# cicely_B_v1.net
KiCad netlist of a schematic drawn in EAGLE
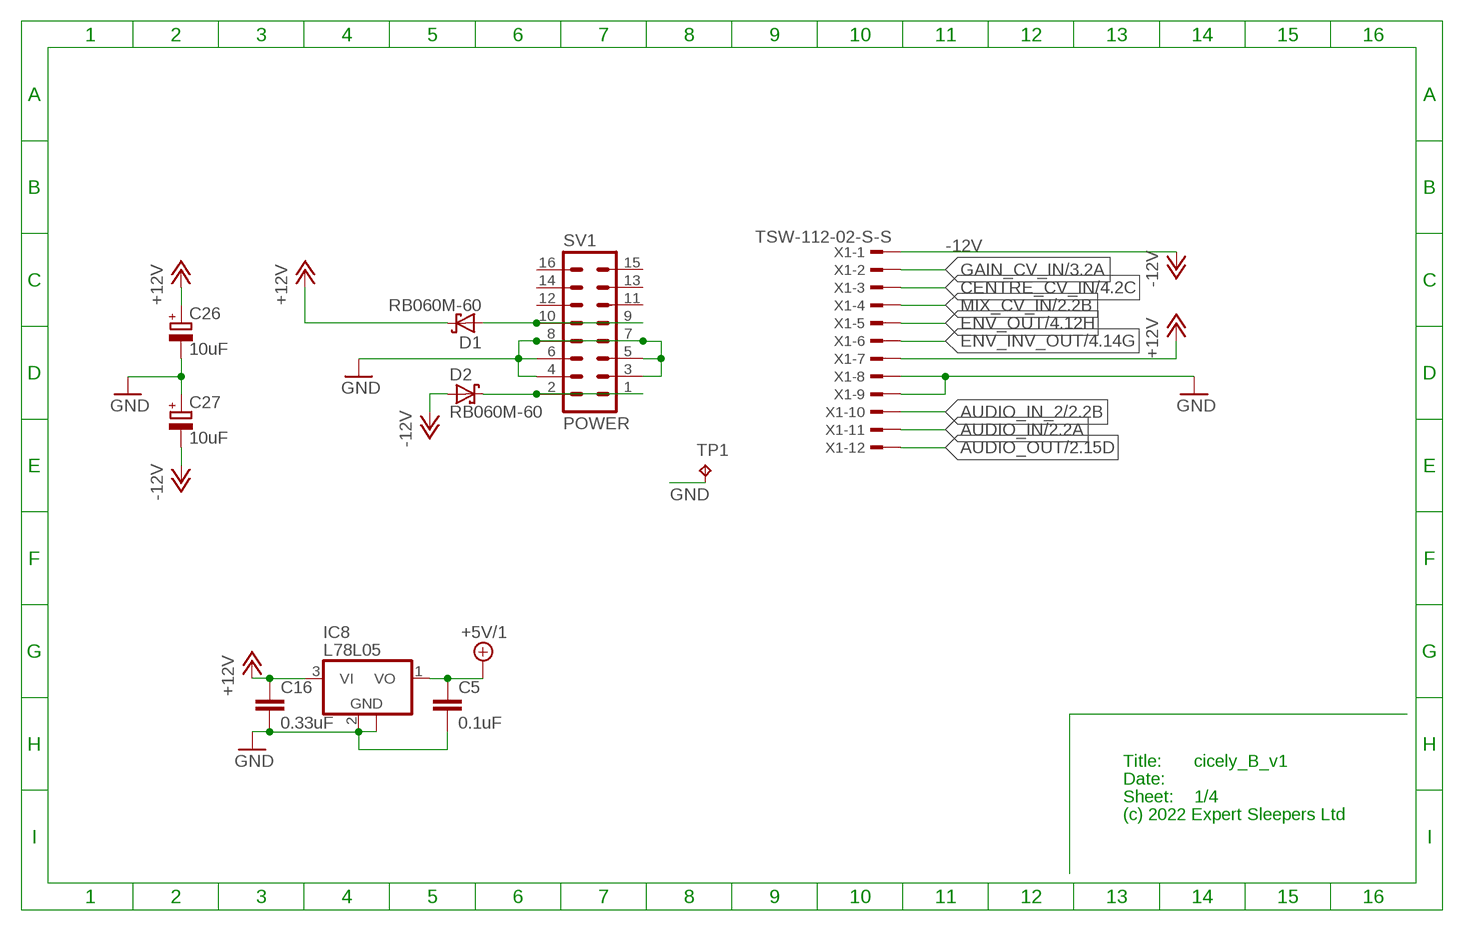
[diagram p0: schematic, sheet 1]
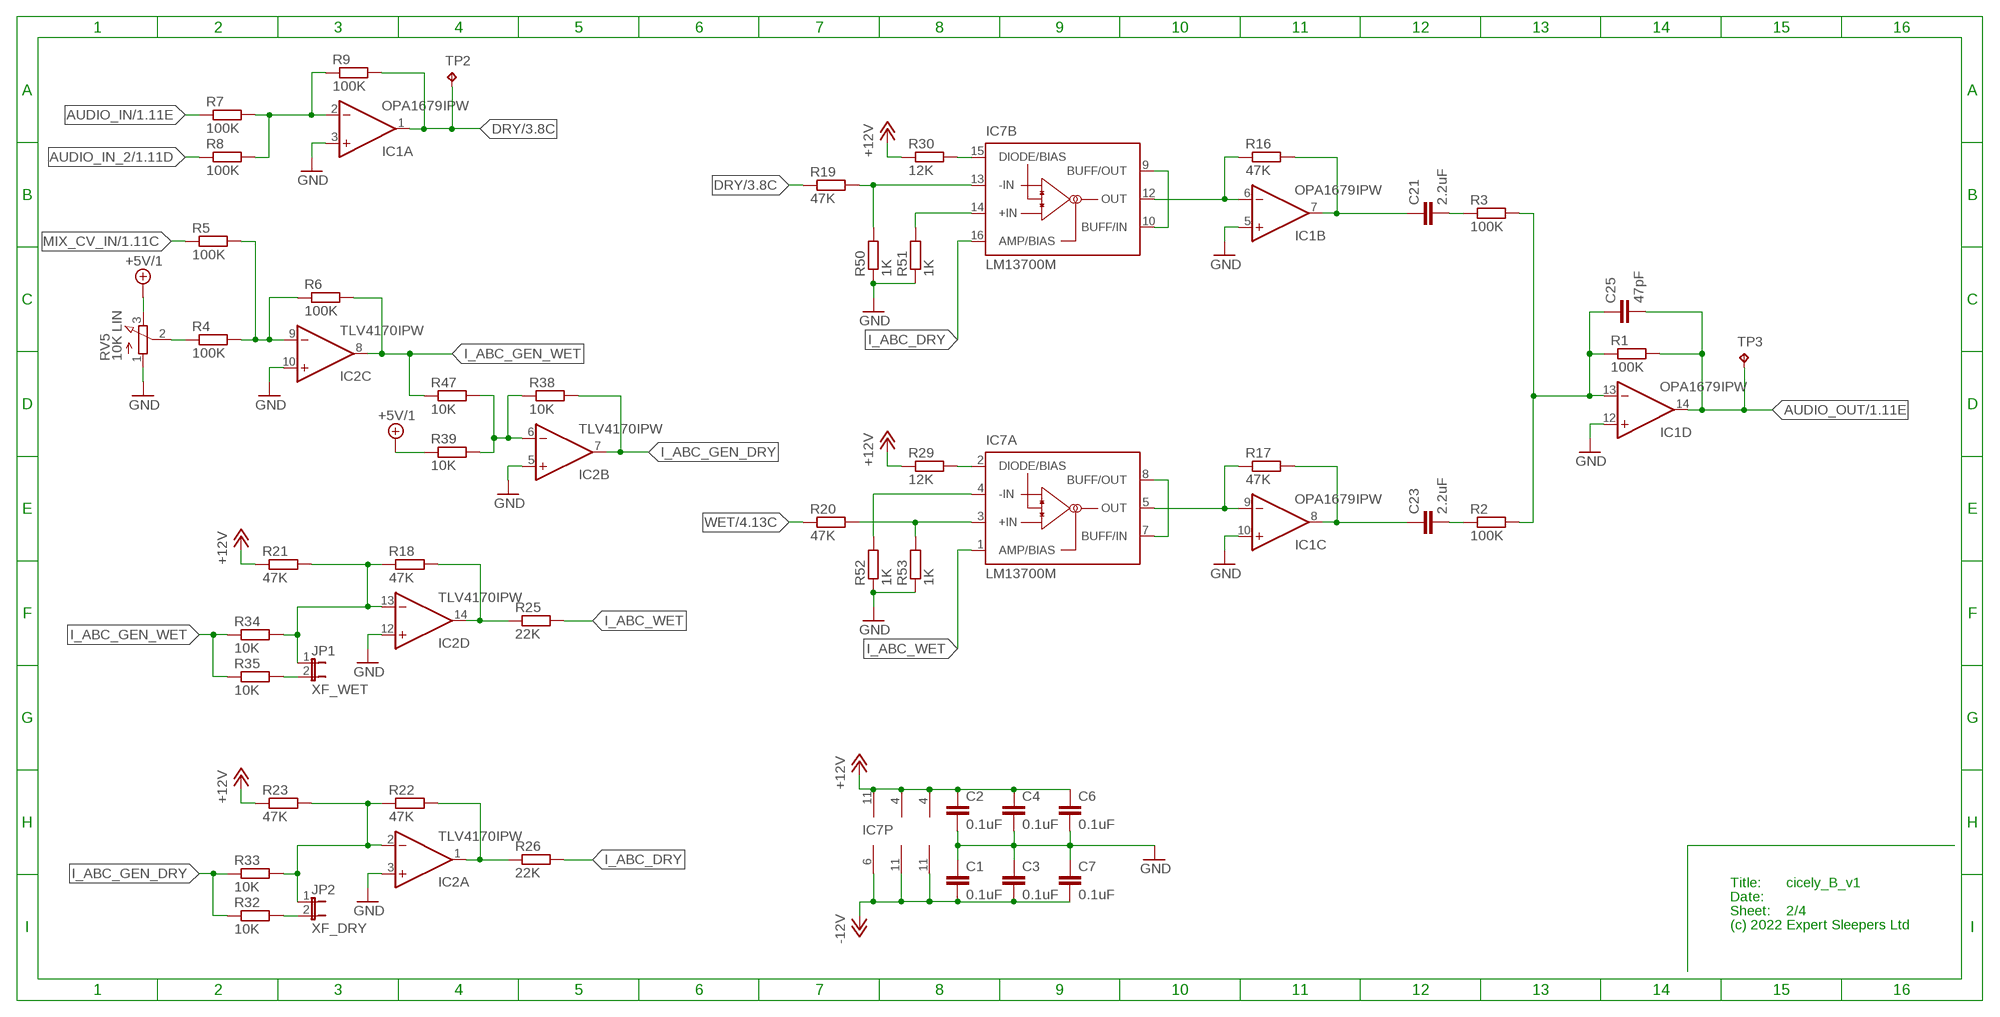
[diagram p1: schematic, sheet 2]
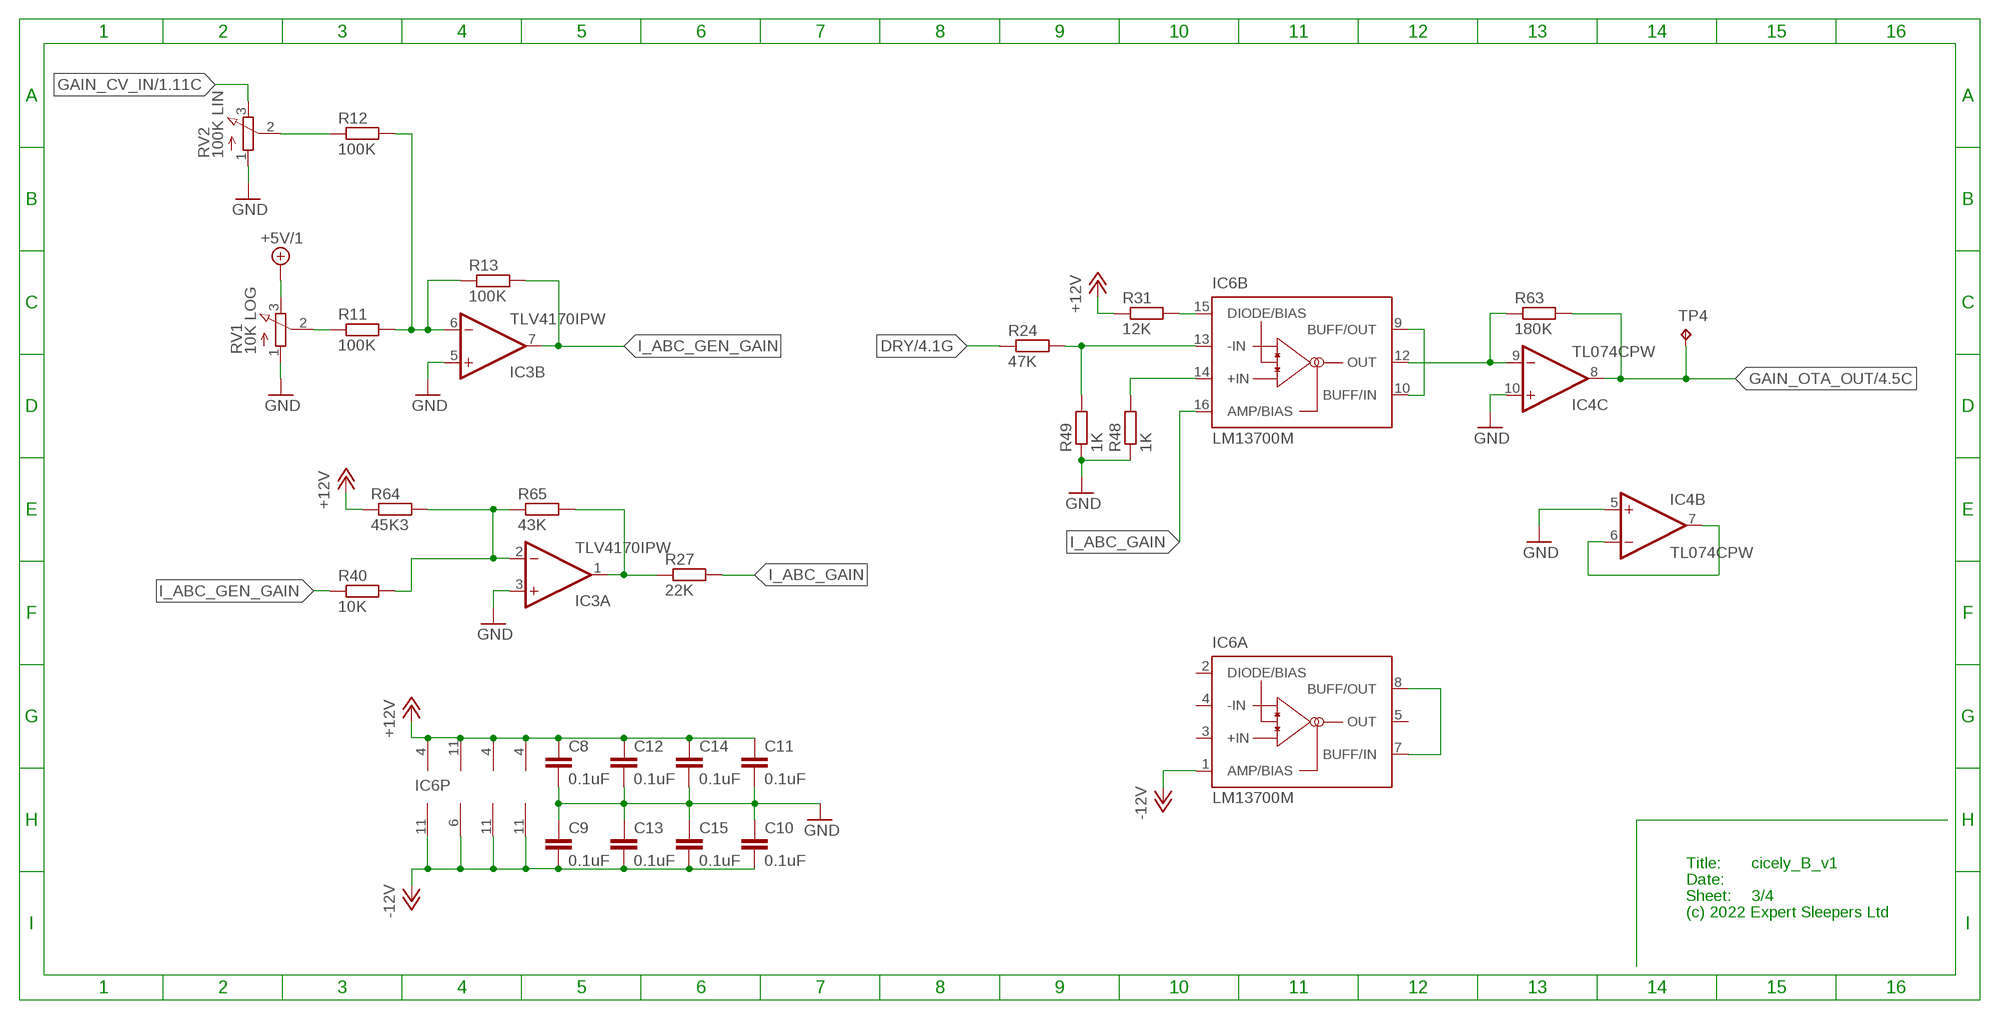
[diagram p2: schematic, sheet 3]
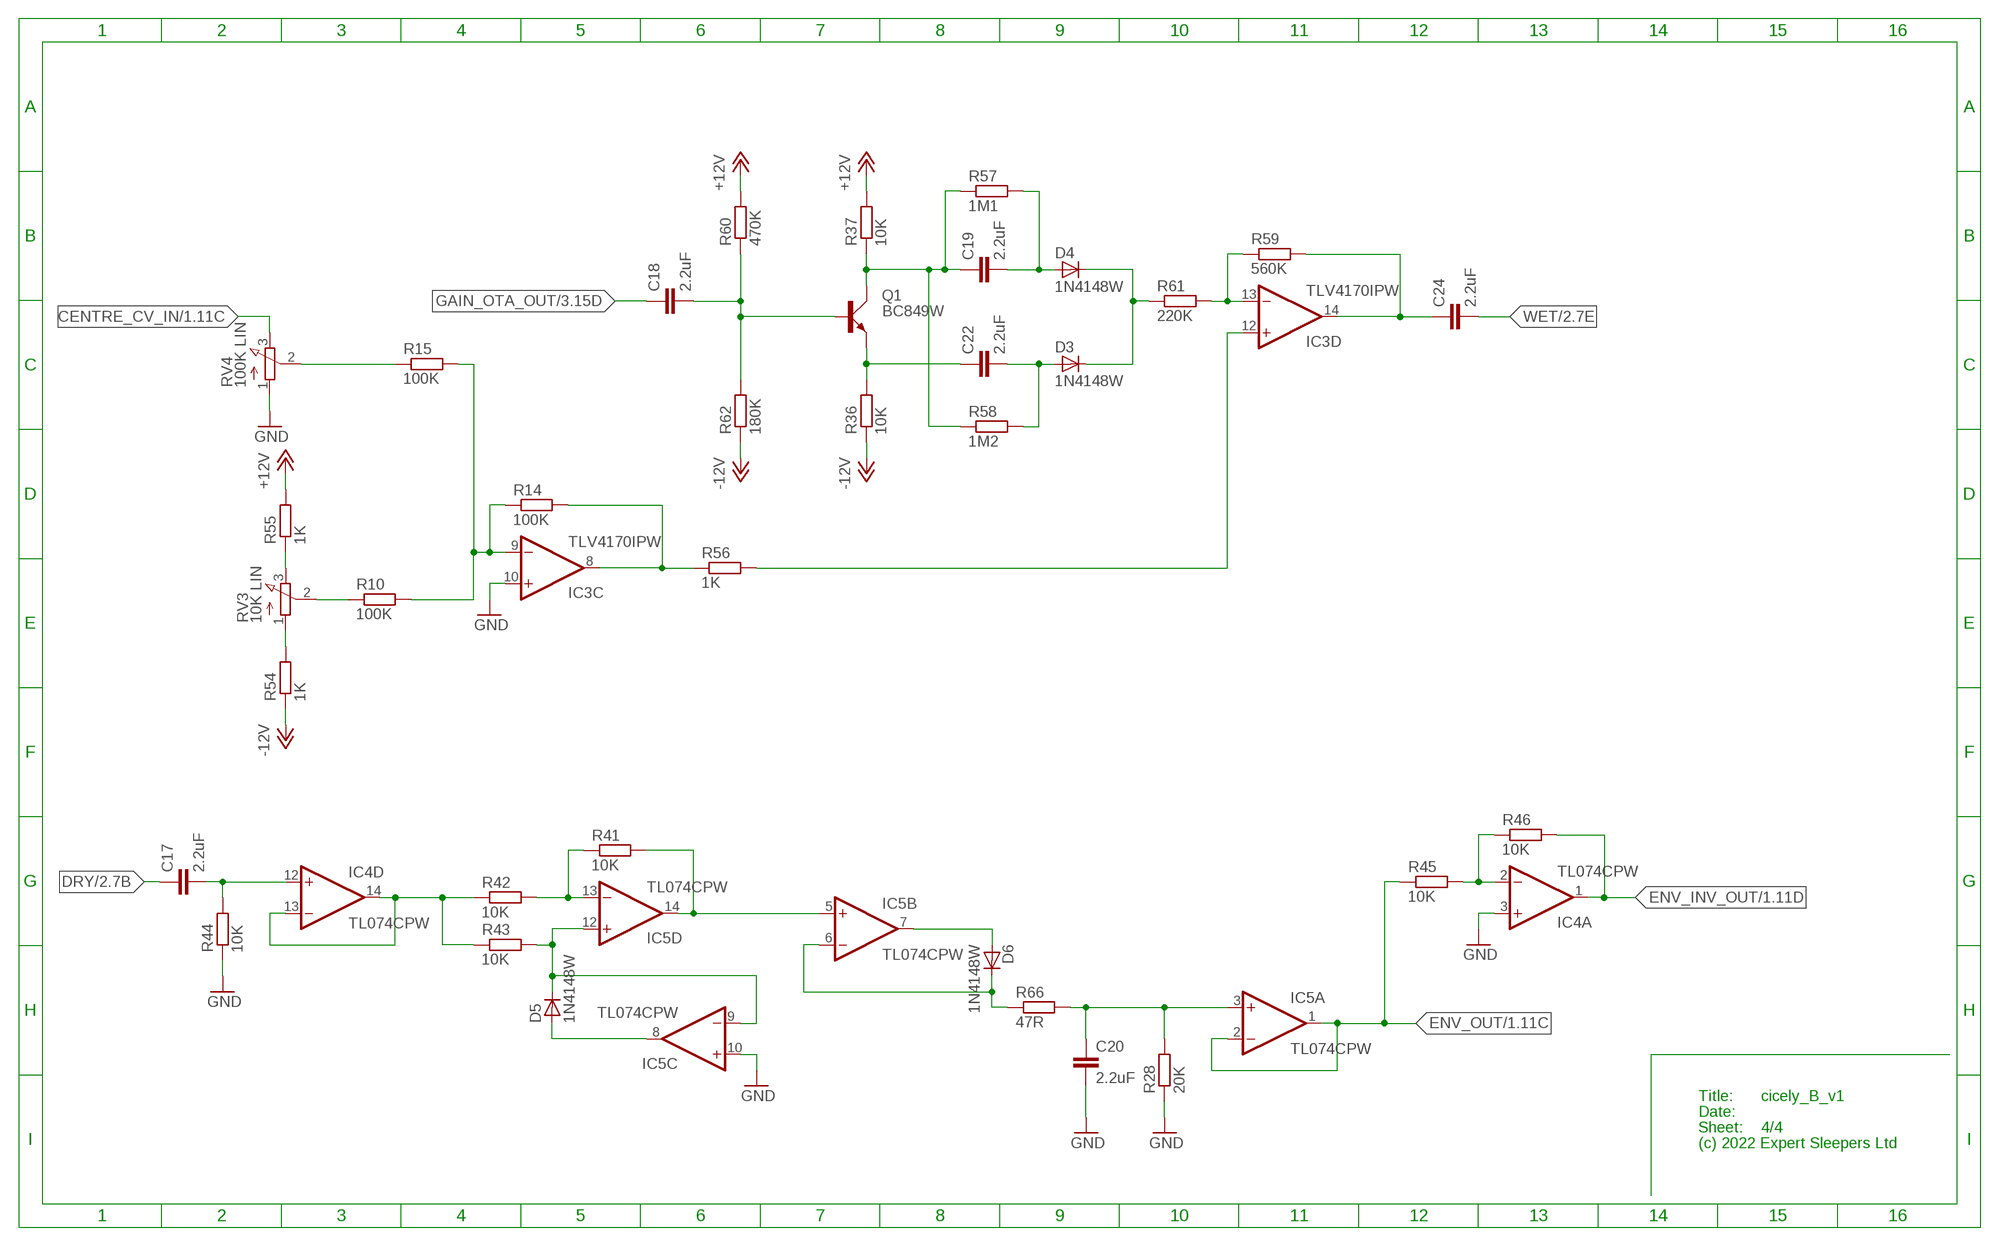
[diagram p3: schematic, sheet 4]

(export (version "E")
  (design (tool "Eeschema 10.0.6"))
  (components
    (comp (ref "C17")
      (value "2.2uF")
      (footprint "eagle-import:C0805")
      (libsource (lib "eagle-import") (part "C-EUC0805"))
    )
    (comp (ref "C18")
      (value "2.2uF")
      (footprint "eagle-import:C0805")
      (libsource (lib "eagle-import") (part "C-EUC0805"))
    )
    (comp (ref "C19")
      (value "2.2uF")
      (footprint "eagle-import:C0805")
      (libsource (lib "eagle-import") (part "C-EUC0805"))
    )
    (comp (ref "C20")
      (value "2.2uF")
      (footprint "eagle-import:C0805")
      (libsource (lib "eagle-import") (part "C-EUC0805"))
    )
    (comp (ref "C22")
      (value "2.2uF")
      (footprint "eagle-import:C0805")
      (libsource (lib "eagle-import") (part "C-EUC0805"))
    )
    (comp (ref "C24")
      (value "2.2uF")
      (footprint "eagle-import:C0805")
      (libsource (lib "eagle-import") (part "C-EUC0805"))
    )
    (comp (ref "D3")
      (value "1N4148W")
      (footprint "eagle-import:SOD123")
      (libsource (lib "eagle-import") (part "1N4148W"))
    )
    (comp (ref "D4")
      (value "1N4148W")
      (footprint "eagle-import:SOD123")
      (libsource (lib "eagle-import") (part "1N4148W"))
    )
    (comp (ref "D5")
      (value "1N4148W")
      (footprint "eagle-import:SOD123")
      (libsource (lib "eagle-import") (part "1N4148W"))
    )
    (comp (ref "D6")
      (value "1N4148W")
      (footprint "eagle-import:SOD123")
      (libsource (lib "eagle-import") (part "1N4148W"))
    )
    (comp (ref "IC3")
      (value "TLV4170IPW")
      (footprint "eagle-import:PW_R-PDSO-G14")
      (libsource (lib "eagle-import") (part "TL074PW"))
    )
    (comp (ref "IC4")
      (value "TL074CPW")
      (footprint "eagle-import:PW_R-PDSO-G14")
      (libsource (lib "eagle-import") (part "TL074PW"))
    )
    (comp (ref "IC5")
      (value "TL074CPW")
      (footprint "eagle-import:PW_R-PDSO-G14")
      (libsource (lib "eagle-import") (part "TL074PW"))
    )
    (comp (ref "Q1")
      (value "BC849W")
      (footprint "eagle-import:SOT323")
      (libsource (lib "eagle-import") (part "BC849W"))
    )
    (comp (ref "R10")
      (value "100K")
      (footprint "eagle-import:R0603")
      (libsource (lib "eagle-import") (part "R-EU_R0603"))
    )
    (comp (ref "R14")
      (value "100K")
      (footprint "eagle-import:R0603")
      (libsource (lib "eagle-import") (part "R-EU_R0603"))
    )
    (comp (ref "R15")
      (value "100K")
      (footprint "eagle-import:R0603")
      (libsource (lib "eagle-import") (part "R-EU_R0603"))
    )
    (comp (ref "R28")
      (value "20K")
      (footprint "eagle-import:R0603")
      (libsource (lib "eagle-import") (part "R-EU_R0603"))
    )
    (comp (ref "R36")
      (value "10K")
      (footprint "eagle-import:R0603")
      (libsource (lib "eagle-import") (part "R-EU_R0603"))
    )
    (comp (ref "R37")
      (value "10K")
      (footprint "eagle-import:R0603")
      (libsource (lib "eagle-import") (part "R-EU_R0603"))
    )
    (comp (ref "R41")
      (value "10K")
      (footprint "eagle-import:R0603")
      (libsource (lib "eagle-import") (part "R-EU_R0603"))
    )
    (comp (ref "R42")
      (value "10K")
      (footprint "eagle-import:R0603")
      (libsource (lib "eagle-import") (part "R-EU_R0603"))
    )
    (comp (ref "R43")
      (value "10K")
      (footprint "eagle-import:R0603")
      (libsource (lib "eagle-import") (part "R-EU_R0603"))
    )
    (comp (ref "R44")
      (value "10K")
      (footprint "eagle-import:R0603")
      (libsource (lib "eagle-import") (part "R-EU_R0603"))
    )
    (comp (ref "R45")
      (value "10K")
      (footprint "eagle-import:R0603")
      (libsource (lib "eagle-import") (part "R-EU_R0603"))
    )
    (comp (ref "R46")
      (value "10K")
      (footprint "eagle-import:R0603")
      (libsource (lib "eagle-import") (part "R-EU_R0603"))
    )
    (comp (ref "R54")
      (value "1K")
      (footprint "eagle-import:R0603")
      (libsource (lib "eagle-import") (part "R-EU_R0603"))
    )
    (comp (ref "R55")
      (value "1K")
      (footprint "eagle-import:R0603")
      (libsource (lib "eagle-import") (part "R-EU_R0603"))
    )
    (comp (ref "R56")
      (value "1K")
      (footprint "eagle-import:R0603")
      (libsource (lib "eagle-import") (part "R-EU_R0603"))
    )
    (comp (ref "R57")
      (value "1M1")
      (footprint "eagle-import:R0603")
      (libsource (lib "eagle-import") (part "R-EU_R0603"))
    )
    (comp (ref "R58")
      (value "1M2")
      (footprint "eagle-import:R0603")
      (libsource (lib "eagle-import") (part "R-EU_R0603"))
    )
    (comp (ref "R59")
      (value "560K")
      (footprint "eagle-import:R0603")
      (libsource (lib "eagle-import") (part "R-EU_R0603"))
    )
    (comp (ref "R60")
      (value "470K")
      (footprint "eagle-import:R0603")
      (libsource (lib "eagle-import") (part "R-EU_R0603"))
    )
    (comp (ref "R61")
      (value "220K")
      (footprint "eagle-import:R0603")
      (libsource (lib "eagle-import") (part "R-EU_R0603"))
    )
    (comp (ref "R62")
      (value "180K")
      (footprint "eagle-import:R0603")
      (libsource (lib "eagle-import") (part "R-EU_R0603"))
    )
    (comp (ref "R66")
      (value "47R")
      (footprint "eagle-import:R0603")
      (libsource (lib "eagle-import") (part "R-EU_R0603"))
    )
    (comp (ref "RV3")
      (value "10K LIN")
      (footprint "eagle-import:RD1610NOA0X")
      (libsource (lib "eagle-import") (part "RD1610NOA0X"))
    )
    (comp (ref "RV4")
      (value "100K LIN")
      (footprint "eagle-import:RD1610NOA0X")
      (libsource (lib "eagle-import") (part "RD1610NOA0X"))
    )
    (comp (ref "C5")
      (value "0.1uF")
      (footprint "eagle-import:C0402")
      (libsource (lib "eagle-import") (part "C-EUC0402"))
    )
    (comp (ref "C16")
      (value "0.33uF")
      (footprint "eagle-import:C0805")
      (libsource (lib "eagle-import") (part "C-EUC0805"))
    )
    (comp (ref "C26")
      (value "10uF")
      (footprint "eagle-import:UD-4X5,8_NICHICON")
      (libsource (lib "eagle-import") (part "CPOL-EUUD-4X5,8"))
    )
    (comp (ref "C27")
      (value "10uF")
      (footprint "eagle-import:UD-4X5,8_NICHICON")
      (libsource (lib "eagle-import") (part "CPOL-EUUD-4X5,8"))
    )
    (comp (ref "D1")
      (value "RB060M-60")
      (footprint "eagle-import:SOD123FL")
      (libsource (lib "eagle-import") (part "RB060M-60"))
    )
    (comp (ref "D2")
      (value "RB060M-60")
      (footprint "eagle-import:SOD123FL")
      (libsource (lib "eagle-import") (part "RB060M-60"))
    )
    (comp (ref "IC8")
      (value "L78L05")
      (footprint "eagle-import:SOT89")
      (libsource (lib "eagle-import") (part "78LF05"))
    )
    (comp (ref "SV1")
      (value "POWER")
      (footprint "eagle-import:ML16")
      (libsource (lib "eagle-import") (part "ML16"))
    )
    (comp (ref "TP1")
      (value "RA2")
      (footprint "eagle-import:P1-13")
      (libsource (lib "eagle-import") (part "TPPAD1-13"))
    )
    (comp (ref "X1")
      (value "TSW-112-02-S-S")
      (footprint "eagle-import:TSW-112-02-S-S")
      (libsource (lib "eagle-import") (part "TSW-112-02-S-S"))
    )
    (comp (ref "C1")
      (value "0.1uF")
      (footprint "eagle-import:C0402")
      (libsource (lib "eagle-import") (part "C-EUC0402"))
    )
    (comp (ref "C2")
      (value "0.1uF")
      (footprint "eagle-import:C0402")
      (libsource (lib "eagle-import") (part "C-EUC0402"))
    )
    (comp (ref "C3")
      (value "0.1uF")
      (footprint "eagle-import:C0402")
      (libsource (lib "eagle-import") (part "C-EUC0402"))
    )
    (comp (ref "C4")
      (value "0.1uF")
      (footprint "eagle-import:C0402")
      (libsource (lib "eagle-import") (part "C-EUC0402"))
    )
    (comp (ref "C6")
      (value "0.1uF")
      (footprint "eagle-import:C0402")
      (libsource (lib "eagle-import") (part "C-EUC0402"))
    )
    (comp (ref "C7")
      (value "0.1uF")
      (footprint "eagle-import:C0402")
      (libsource (lib "eagle-import") (part "C-EUC0402"))
    )
    (comp (ref "C21")
      (value "2.2uF")
      (footprint "eagle-import:C0805")
      (libsource (lib "eagle-import") (part "C-EUC0805"))
    )
    (comp (ref "C23")
      (value "2.2uF")
      (footprint "eagle-import:C0805")
      (libsource (lib "eagle-import") (part "C-EUC0805"))
    )
    (comp (ref "C25")
      (value "47pF")
      (footprint "eagle-import:C0603")
      (libsource (lib "eagle-import") (part "C-EUC0603"))
    )
    (comp (ref "IC1")
      (value "OPA1679IPW")
      (footprint "eagle-import:PW_R-PDSO-G14")
      (libsource (lib "eagle-import") (part "TL074PW"))
    )
    (comp (ref "IC2")
      (value "TLV4170IPW")
      (footprint "eagle-import:PW_R-PDSO-G14")
      (libsource (lib "eagle-import") (part "TL074PW"))
    )
    (comp (ref "IC7")
      (value "LM13700M")
      (footprint "eagle-import:SO16")
      (libsource (lib "eagle-import") (part "LM13700M"))
    )
    (comp (ref "JP1")
      (value "XF_WET")
      (footprint "eagle-import:JP1")
      (libsource (lib "eagle-import") (part "JP1E"))
    )
    (comp (ref "JP2")
      (value "XF_DRY")
      (footprint "eagle-import:JP1")
      (libsource (lib "eagle-import") (part "JP1E"))
    )
    (comp (ref "R1")
      (value "100K")
      (footprint "eagle-import:R0603")
      (libsource (lib "eagle-import") (part "R-EU_R0603"))
    )
    (comp (ref "R2")
      (value "100K")
      (footprint "eagle-import:R0603")
      (libsource (lib "eagle-import") (part "R-EU_R0603"))
    )
    (comp (ref "R3")
      (value "100K")
      (footprint "eagle-import:R0603")
      (libsource (lib "eagle-import") (part "R-EU_R0603"))
    )
    (comp (ref "R4")
      (value "100K")
      (footprint "eagle-import:R0603")
      (libsource (lib "eagle-import") (part "R-EU_R0603"))
    )
    (comp (ref "R5")
      (value "100K")
      (footprint "eagle-import:R0603")
      (libsource (lib "eagle-import") (part "R-EU_R0603"))
    )
    (comp (ref "R6")
      (value "100K")
      (footprint "eagle-import:R0603")
      (libsource (lib "eagle-import") (part "R-EU_R0603"))
    )
    (comp (ref "R7")
      (value "100K")
      (footprint "eagle-import:R0603")
      (libsource (lib "eagle-import") (part "R-EU_R0603"))
    )
    (comp (ref "R8")
      (value "100K")
      (footprint "eagle-import:R0603")
      (libsource (lib "eagle-import") (part "R-EU_R0603"))
    )
    (comp (ref "R9")
      (value "100K")
      (footprint "eagle-import:R0603")
      (libsource (lib "eagle-import") (part "R-EU_R0603"))
    )
    (comp (ref "R16")
      (value "47K")
      (footprint "eagle-import:R0603")
      (libsource (lib "eagle-import") (part "R-EU_R0603"))
    )
    (comp (ref "R17")
      (value "47K")
      (footprint "eagle-import:R0603")
      (libsource (lib "eagle-import") (part "R-EU_R0603"))
    )
    (comp (ref "R18")
      (value "47K")
      (footprint "eagle-import:R0603")
      (libsource (lib "eagle-import") (part "R-EU_R0603"))
    )
    (comp (ref "R19")
      (value "47K")
      (footprint "eagle-import:R0603")
      (libsource (lib "eagle-import") (part "R-EU_R0603"))
    )
    (comp (ref "R20")
      (value "47K")
      (footprint "eagle-import:R0603")
      (libsource (lib "eagle-import") (part "R-EU_R0603"))
    )
    (comp (ref "R21")
      (value "47K")
      (footprint "eagle-import:R0603")
      (libsource (lib "eagle-import") (part "R-EU_R0603"))
    )
    (comp (ref "R22")
      (value "47K")
      (footprint "eagle-import:R0603")
      (libsource (lib "eagle-import") (part "R-EU_R0603"))
    )
    (comp (ref "R23")
      (value "47K")
      (footprint "eagle-import:R0603")
      (libsource (lib "eagle-import") (part "R-EU_R0603"))
    )
    (comp (ref "R25")
      (value "22K")
      (footprint "eagle-import:R0603")
      (libsource (lib "eagle-import") (part "R-EU_R0603"))
    )
    (comp (ref "R26")
      (value "22K")
      (footprint "eagle-import:R0603")
      (libsource (lib "eagle-import") (part "R-EU_R0603"))
    )
    (comp (ref "R29")
      (value "12K")
      (footprint "eagle-import:R0603")
      (libsource (lib "eagle-import") (part "R-EU_R0603"))
    )
    (comp (ref "R30")
      (value "12K")
      (footprint "eagle-import:R0603")
      (libsource (lib "eagle-import") (part "R-EU_R0603"))
    )
    (comp (ref "R32")
      (value "10K")
      (footprint "eagle-import:R0603")
      (libsource (lib "eagle-import") (part "R-EU_R0603"))
    )
    (comp (ref "R33")
      (value "10K")
      (footprint "eagle-import:R0603")
      (libsource (lib "eagle-import") (part "R-EU_R0603"))
    )
    (comp (ref "R34")
      (value "10K")
      (footprint "eagle-import:R0603")
      (libsource (lib "eagle-import") (part "R-EU_R0603"))
    )
    (comp (ref "R35")
      (value "10K")
      (footprint "eagle-import:R0603")
      (libsource (lib "eagle-import") (part "R-EU_R0603"))
    )
    (comp (ref "R38")
      (value "10K")
      (footprint "eagle-import:R0603")
      (libsource (lib "eagle-import") (part "R-EU_R0603"))
    )
    (comp (ref "R39")
      (value "10K")
      (footprint "eagle-import:R0603")
      (libsource (lib "eagle-import") (part "R-EU_R0603"))
    )
    (comp (ref "R47")
      (value "10K")
      (footprint "eagle-import:R0603")
      (libsource (lib "eagle-import") (part "R-EU_R0603"))
    )
    (comp (ref "R50")
      (value "1K")
      (footprint "eagle-import:R0603")
      (libsource (lib "eagle-import") (part "R-EU_R0603"))
    )
    (comp (ref "R51")
      (value "1K")
      (footprint "eagle-import:R0603")
      (libsource (lib "eagle-import") (part "R-EU_R0603"))
    )
    (comp (ref "R52")
      (value "1K")
      (footprint "eagle-import:R0603")
      (libsource (lib "eagle-import") (part "R-EU_R0603"))
    )
    (comp (ref "R53")
      (value "1K")
      (footprint "eagle-import:R0603")
      (libsource (lib "eagle-import") (part "R-EU_R0603"))
    )
    (comp (ref "RV5")
      (value "10K LIN")
      (footprint "eagle-import:RD1610NOA0X")
      (libsource (lib "eagle-import") (part "RD1610NOA0X"))
    )
    (comp (ref "TP2")
      (value "RA2")
      (footprint "eagle-import:P1-13")
      (libsource (lib "eagle-import") (part "TPPAD1-13"))
    )
    (comp (ref "TP3")
      (value "RA2")
      (footprint "eagle-import:P1-13")
      (libsource (lib "eagle-import") (part "TPPAD1-13"))
    )
    (comp (ref "C8")
      (value "0.1uF")
      (footprint "eagle-import:C0402")
      (libsource (lib "eagle-import") (part "C-EUC0402"))
    )
    (comp (ref "C9")
      (value "0.1uF")
      (footprint "eagle-import:C0402")
      (libsource (lib "eagle-import") (part "C-EUC0402"))
    )
    (comp (ref "C10")
      (value "0.1uF")
      (footprint "eagle-import:C0402")
      (libsource (lib "eagle-import") (part "C-EUC0402"))
    )
    (comp (ref "C11")
      (value "0.1uF")
      (footprint "eagle-import:C0402")
      (libsource (lib "eagle-import") (part "C-EUC0402"))
    )
    (comp (ref "C12")
      (value "0.1uF")
      (footprint "eagle-import:C0402")
      (libsource (lib "eagle-import") (part "C-EUC0402"))
    )
    (comp (ref "C13")
      (value "0.1uF")
      (footprint "eagle-import:C0402")
      (libsource (lib "eagle-import") (part "C-EUC0402"))
    )
    (comp (ref "C14")
      (value "0.1uF")
      (footprint "eagle-import:C0402")
      (libsource (lib "eagle-import") (part "C-EUC0402"))
    )
    (comp (ref "C15")
      (value "0.1uF")
      (footprint "eagle-import:C0402")
      (libsource (lib "eagle-import") (part "C-EUC0402"))
    )
    (comp (ref "IC6")
      (value "LM13700M")
      (footprint "eagle-import:SO16")
      (libsource (lib "eagle-import") (part "LM13700M"))
    )
    (comp (ref "R11")
      (value "100K")
      (footprint "eagle-import:R0603")
      (libsource (lib "eagle-import") (part "R-EU_R0603"))
    )
    (comp (ref "R12")
      (value "100K")
      (footprint "eagle-import:R0603")
      (libsource (lib "eagle-import") (part "R-EU_R0603"))
    )
    (comp (ref "R13")
      (value "100K")
      (footprint "eagle-import:R0603")
      (libsource (lib "eagle-import") (part "R-EU_R0603"))
    )
    (comp (ref "R24")
      (value "47K")
      (footprint "eagle-import:R0603")
      (libsource (lib "eagle-import") (part "R-EU_R0603"))
    )
    (comp (ref "R27")
      (value "22K")
      (footprint "eagle-import:R0603")
      (libsource (lib "eagle-import") (part "R-EU_R0603"))
    )
    (comp (ref "R31")
      (value "12K")
      (footprint "eagle-import:R0603")
      (libsource (lib "eagle-import") (part "R-EU_R0603"))
    )
    (comp (ref "R40")
      (value "10K")
      (footprint "eagle-import:R0603")
      (libsource (lib "eagle-import") (part "R-EU_R0603"))
    )
    (comp (ref "R48")
      (value "1K")
      (footprint "eagle-import:R0603")
      (libsource (lib "eagle-import") (part "R-EU_R0603"))
    )
    (comp (ref "R49")
      (value "1K")
      (footprint "eagle-import:R0603")
      (libsource (lib "eagle-import") (part "R-EU_R0603"))
    )
    (comp (ref "R63")
      (value "180K")
      (footprint "eagle-import:R0603")
      (libsource (lib "eagle-import") (part "R-EU_R0603"))
    )
    (comp (ref "R64")
      (value "45K3")
      (footprint "eagle-import:R0603")
      (libsource (lib "eagle-import") (part "R-EU_R0603"))
    )
    (comp (ref "R65")
      (value "43K")
      (footprint "eagle-import:R0603")
      (libsource (lib "eagle-import") (part "R-EU_R0603"))
    )
    (comp (ref "RV1")
      (value "10K LOG")
      (footprint "eagle-import:RD1610NOA0X")
      (libsource (lib "eagle-import") (part "RD1610NOA0X"))
    )
    (comp (ref "RV2")
      (value "100K LIN")
      (footprint "eagle-import:RD1610NOA0X")
      (libsource (lib "eagle-import") (part "RD1610NOA0X"))
    )
    (comp (ref "TP4")
      (value "RA2")
      (footprint "eagle-import:P1-13")
      (libsource (lib "eagle-import") (part "TPPAD1-13"))
    )
  )
  (nets
    (net (code "1") (name "+5V{slash}1") (class "Default")
      (node (ref "C5") (pin "1") (pinfunction "1_1") (pintype "passive"))
      (node (ref "IC8") (pin "1") (pinfunction "VO_1") (pintype "passive"))
      (node (ref "R39") (pin "1") (pinfunction "1_1") (pintype "passive"))
      (node (ref "RV1") (pin "3") (pinfunction "E_3") (pintype "passive"))
      (node (ref "RV5") (pin "3") (pinfunction "E_3") (pintype "passive"))
    )
    (net (code "2") (name "+12V") (class "Default")
      (node (ref "C11") (pin "1") (pinfunction "1_1") (pintype "passive"))
      (node (ref "C12") (pin "1") (pinfunction "1_1") (pintype "passive"))
      (node (ref "C14") (pin "1") (pinfunction "1_1") (pintype "passive"))
      (node (ref "C16") (pin "1") (pinfunction "1_1") (pintype "passive"))
      (node (ref "C2") (pin "1") (pinfunction "1_1") (pintype "passive"))
      (node (ref "C26") (pin "+") (pinfunction "+_+") (pintype "passive"))
      (node (ref "C4") (pin "1") (pinfunction "1_1") (pintype "passive"))
      (node (ref "C6") (pin "1") (pinfunction "1_1") (pintype "passive"))
      (node (ref "C8") (pin "1") (pinfunction "1_1") (pintype "passive"))
      (node (ref "D1") (pin "C") (pinfunction "C_C") (pintype "passive"))
      (node (ref "IC1") (pin "4") (pinfunction "V+_4") (pintype "power_in"))
      (node (ref "IC2") (pin "4") (pinfunction "V+_4") (pintype "power_in"))
      (node (ref "IC3") (pin "4") (pinfunction "V+_4") (pintype "power_in"))
      (node (ref "IC4") (pin "4") (pinfunction "V+_4") (pintype "power_in"))
      (node (ref "IC5") (pin "4") (pinfunction "V+_4") (pintype "power_in"))
      (node (ref "IC6") (pin "11") (pinfunction "V+_11") (pintype "power_in"))
      (node (ref "IC7") (pin "11") (pinfunction "V+_11") (pintype "power_in"))
      (node (ref "IC8") (pin "3") (pinfunction "VI_3") (pintype "input"))
      (node (ref "R21") (pin "1") (pinfunction "1_1") (pintype "passive"))
      (node (ref "R23") (pin "1") (pinfunction "1_1") (pintype "passive"))
      (node (ref "R29") (pin "1") (pinfunction "1_1") (pintype "passive"))
      (node (ref "R30") (pin "1") (pinfunction "1_1") (pintype "passive"))
      (node (ref "R31") (pin "1") (pinfunction "1_1") (pintype "passive"))
      (node (ref "R37") (pin "2") (pinfunction "2_2") (pintype "passive"))
      (node (ref "R55") (pin "2") (pinfunction "2_2") (pintype "passive"))
      (node (ref "R60") (pin "2") (pinfunction "2_2") (pintype "passive"))
      (node (ref "R64") (pin "1") (pinfunction "1_1") (pintype "passive"))
      (node (ref "X1") (pin "7") (pinfunction "1_7") (pintype "passive"))
    )
    (net (code "3") (name "-12V") (class "Default")
      (node (ref "C1") (pin "2") (pinfunction "2_2") (pintype "passive"))
      (node (ref "C10") (pin "2") (pinfunction "2_2") (pintype "passive"))
      (node (ref "C13") (pin "2") (pinfunction "2_2") (pintype "passive"))
      (node (ref "C15") (pin "2") (pinfunction "2_2") (pintype "passive"))
      (node (ref "C27") (pin "-") (pinfunction "-_-") (pintype "passive"))
      (node (ref "C3") (pin "2") (pinfunction "2_2") (pintype "passive"))
      (node (ref "C7") (pin "2") (pinfunction "2_2") (pintype "passive"))
      (node (ref "C9") (pin "2") (pinfunction "2_2") (pintype "passive"))
      (node (ref "D2") (pin "A") (pinfunction "A_A") (pintype "passive"))
      (node (ref "IC1") (pin "11") (pinfunction "V-_11") (pintype "power_in"))
      (node (ref "IC2") (pin "11") (pinfunction "V-_11") (pintype "power_in"))
      (node (ref "IC3") (pin "11") (pinfunction "V-_11") (pintype "power_in"))
      (node (ref "IC4") (pin "11") (pinfunction "V-_11") (pintype "power_in"))
      (node (ref "IC5") (pin "11") (pinfunction "V-_11") (pintype "power_in"))
      (node (ref "IC6") (pin "1") (pinfunction "AMP/BIAS_1") (pintype "passive"))
      (node (ref "IC6") (pin "6") (pinfunction "V-_6") (pintype "power_in"))
      (node (ref "IC7") (pin "6") (pinfunction "V-_6") (pintype "power_in"))
      (node (ref "R36") (pin "1") (pinfunction "1_1") (pintype "passive"))
      (node (ref "R54") (pin "1") (pinfunction "1_1") (pintype "passive"))
      (node (ref "R62") (pin "1") (pinfunction "1_1") (pintype "passive"))
      (node (ref "X1") (pin "1") (pinfunction "1_1") (pintype "passive"))
    )
    (net (code "4") (name "AUDIO_IN") (class "Default")
      (node (ref "R7") (pin "1") (pinfunction "1_1") (pintype "passive"))
      (node (ref "X1") (pin "11") (pinfunction "1_11") (pintype "passive"))
    )
    (net (code "5") (name "AUDIO_IN_2") (class "Default")
      (node (ref "R8") (pin "1") (pinfunction "1_1") (pintype "passive"))
      (node (ref "X1") (pin "10") (pinfunction "1_10") (pintype "passive"))
    )
    (net (code "6") (name "AUDIO_OUT") (class "Default")
      (node (ref "C25") (pin "2") (pinfunction "2_2") (pintype "passive"))
      (node (ref "IC1") (pin "14") (pinfunction "OUT_14") (pintype "output"))
      (node (ref "R1") (pin "2") (pinfunction "2_2") (pintype "passive"))
      (node (ref "TP3") (pin "TP") (pinfunction "TP_TP") (pintype "input"))
      (node (ref "X1") (pin "12") (pinfunction "1_12") (pintype "passive"))
    )
    (net (code "7") (name "CENTRE_CV_IN") (class "Default")
      (node (ref "RV4") (pin "3") (pinfunction "E_3") (pintype "passive"))
      (node (ref "X1") (pin "3") (pinfunction "1_3") (pintype "passive"))
    )
    (net (code "8") (name "DRY") (class "Default")
      (node (ref "C17") (pin "1") (pinfunction "1_1") (pintype "passive"))
      (node (ref "IC1") (pin "1") (pinfunction "OUT_1") (pintype "output"))
      (node (ref "R19") (pin "1") (pinfunction "1_1") (pintype "passive"))
      (node (ref "R24") (pin "1") (pinfunction "1_1") (pintype "passive"))
      (node (ref "R9") (pin "2") (pinfunction "2_2") (pintype "passive"))
      (node (ref "TP2") (pin "TP") (pinfunction "TP_TP") (pintype "input"))
    )
    (net (code "9") (name "ENV_INV_OUT") (class "Default")
      (node (ref "IC4") (pin "1") (pinfunction "OUT_1") (pintype "output"))
      (node (ref "R46") (pin "2") (pinfunction "2_2") (pintype "passive"))
      (node (ref "X1") (pin "6") (pinfunction "1_6") (pintype "passive"))
    )
    (net (code "10") (name "ENV_OUT") (class "Default")
      (node (ref "IC5") (pin "1") (pinfunction "OUT_1") (pintype "output"))
      (node (ref "IC5") (pin "2") (pinfunction "-IN_2") (pintype "input"))
      (node (ref "R45") (pin "1") (pinfunction "1_1") (pintype "passive"))
      (node (ref "X1") (pin "5") (pinfunction "1_5") (pintype "passive"))
    )
    (net (code "11") (name "GAIN_CV_IN") (class "Default")
      (node (ref "RV2") (pin "3") (pinfunction "E_3") (pintype "passive"))
      (node (ref "X1") (pin "2") (pinfunction "1_2") (pintype "passive"))
    )
    (net (code "12") (name "GAIN_OTA_OUT") (class "Default")
      (node (ref "C18") (pin "1") (pinfunction "1_1") (pintype "passive"))
      (node (ref "IC4") (pin "8") (pinfunction "OUT_8") (pintype "output"))
      (node (ref "R63") (pin "2") (pinfunction "2_2") (pintype "passive"))
      (node (ref "TP4") (pin "TP") (pinfunction "TP_TP") (pintype "input"))
    )
    (net (code "13") (name "GND") (class "Default")
      (node (ref "C1") (pin "1") (pinfunction "1_1") (pintype "passive"))
      (node (ref "C10") (pin "1") (pinfunction "1_1") (pintype "passive"))
      (node (ref "C11") (pin "2") (pinfunction "2_2") (pintype "passive"))
      (node (ref "C12") (pin "2") (pinfunction "2_2") (pintype "passive"))
      (node (ref "C13") (pin "1") (pinfunction "1_1") (pintype "passive"))
      (node (ref "C14") (pin "2") (pinfunction "2_2") (pintype "passive"))
      (node (ref "C15") (pin "1") (pinfunction "1_1") (pintype "passive"))
      (node (ref "C16") (pin "2") (pinfunction "2_2") (pintype "passive"))
      (node (ref "C2") (pin "2") (pinfunction "2_2") (pintype "passive"))
      (node (ref "C20") (pin "2") (pinfunction "2_2") (pintype "passive"))
      (node (ref "C26") (pin "-") (pinfunction "-_-") (pintype "passive"))
      (node (ref "C27") (pin "+") (pinfunction "+_+") (pintype "passive"))
      (node (ref "C3") (pin "1") (pinfunction "1_1") (pintype "passive"))
      (node (ref "C4") (pin "2") (pinfunction "2_2") (pintype "passive"))
      (node (ref "C5") (pin "2") (pinfunction "2_2") (pintype "passive"))
      (node (ref "C6") (pin "2") (pinfunction "2_2") (pintype "passive"))
      (node (ref "C7") (pin "1") (pinfunction "1_1") (pintype "passive"))
      (node (ref "C8") (pin "2") (pinfunction "2_2") (pintype "passive"))
      (node (ref "C9") (pin "1") (pinfunction "1_1") (pintype "passive"))
      (node (ref "IC1") (pin "10") (pinfunction "+IN_10") (pintype "input"))
      (node (ref "IC1") (pin "12") (pinfunction "+IN_12") (pintype "input"))
      (node (ref "IC1") (pin "3") (pinfunction "+IN_3") (pintype "input"))
      (node (ref "IC1") (pin "5") (pinfunction "+IN_5") (pintype "input"))
      (node (ref "IC2") (pin "10") (pinfunction "+IN_10") (pintype "input"))
      (node (ref "IC2") (pin "12") (pinfunction "+IN_12") (pintype "input"))
      (node (ref "IC2") (pin "3") (pinfunction "+IN_3") (pintype "input"))
      (node (ref "IC2") (pin "5") (pinfunction "+IN_5") (pintype "input"))
      (node (ref "IC3") (pin "10") (pinfunction "+IN_10") (pintype "input"))
      (node (ref "IC3") (pin "3") (pinfunction "+IN_3") (pintype "input"))
      (node (ref "IC3") (pin "5") (pinfunction "+IN_5") (pintype "input"))
      (node (ref "IC4") (pin "10") (pinfunction "+IN_10") (pintype "input"))
      (node (ref "IC4") (pin "3") (pinfunction "+IN_3") (pintype "input"))
      (node (ref "IC4") (pin "5") (pinfunction "+IN_5") (pintype "input"))
      (node (ref "IC5") (pin "10") (pinfunction "+IN_10") (pintype "input"))
      (node (ref "IC8") (pin "2") (pinfunction "GND_2") (pintype "passive"))
      (node (ref "IC8") (pin "2@1") (pinfunction "GND_2@1") (pintype "passive"))
      (node (ref "R28") (pin "1") (pinfunction "1_1") (pintype "passive"))
      (node (ref "R44") (pin "1") (pinfunction "1_1") (pintype "passive"))
      (node (ref "R48") (pin "1") (pinfunction "1_1") (pintype "passive"))
      (node (ref "R49") (pin "1") (pinfunction "1_1") (pintype "passive"))
      (node (ref "R50") (pin "1") (pinfunction "1_1") (pintype "passive"))
      (node (ref "R51") (pin "1") (pinfunction "1_1") (pintype "passive"))
      (node (ref "R52") (pin "1") (pinfunction "1_1") (pintype "passive"))
      (node (ref "R53") (pin "1") (pinfunction "1_1") (pintype "passive"))
      (node (ref "RV1") (pin "1") (pinfunction "A_1") (pintype "passive"))
      (node (ref "RV2") (pin "1") (pinfunction "A_1") (pintype "passive"))
      (node (ref "RV4") (pin "1") (pinfunction "A_1") (pintype "passive"))
      (node (ref "RV5") (pin "1") (pinfunction "A_1") (pintype "passive"))
      (node (ref "SV1") (pin "3") (pinfunction "3_3") (pintype "passive"))
      (node (ref "SV1") (pin "4") (pinfunction "4_4") (pintype "passive"))
      (node (ref "SV1") (pin "5") (pinfunction "5_5") (pintype "passive"))
      (node (ref "SV1") (pin "6") (pinfunction "6_6") (pintype "passive"))
      (node (ref "SV1") (pin "7") (pinfunction "7_7") (pintype "passive"))
      (node (ref "SV1") (pin "8") (pinfunction "8_8") (pintype "passive"))
      (node (ref "TP1") (pin "TP") (pinfunction "TP_TP") (pintype "input"))
      (node (ref "X1") (pin "8") (pinfunction "1_8") (pintype "passive"))
      (node (ref "X1") (pin "9") (pinfunction "1_9") (pintype "passive"))
    )
    (net (code "14") (name "I_ABC_DRY") (class "Default")
      (node (ref "IC7") (pin "16") (pinfunction "AMP/BIAS_16") (pintype "passive"))
      (node (ref "R26") (pin "2") (pinfunction "2_2") (pintype "passive"))
    )
    (net (code "15") (name "I_ABC_GAIN") (class "Default")
      (node (ref "IC6") (pin "16") (pinfunction "AMP/BIAS_16") (pintype "passive"))
      (node (ref "R27") (pin "2") (pinfunction "2_2") (pintype "passive"))
    )
    (net (code "16") (name "I_ABC_GEN_DRY") (class "Default")
      (node (ref "IC2") (pin "7") (pinfunction "OUT_7") (pintype "output"))
      (node (ref "R32") (pin "1") (pinfunction "1_1") (pintype "passive"))
      (node (ref "R33") (pin "1") (pinfunction "1_1") (pintype "passive"))
      (node (ref "R38") (pin "2") (pinfunction "2_2") (pintype "passive"))
    )
    (net (code "17") (name "I_ABC_GEN_GAIN") (class "Default")
      (node (ref "IC3") (pin "7") (pinfunction "OUT_7") (pintype "output"))
      (node (ref "R13") (pin "2") (pinfunction "2_2") (pintype "passive"))
      (node (ref "R40") (pin "1") (pinfunction "1_1") (pintype "passive"))
    )
    (net (code "18") (name "I_ABC_GEN_WET") (class "Default")
      (node (ref "IC2") (pin "8") (pinfunction "OUT_8") (pintype "output"))
      (node (ref "R34") (pin "1") (pinfunction "1_1") (pintype "passive"))
      (node (ref "R35") (pin "1") (pinfunction "1_1") (pintype "passive"))
      (node (ref "R47") (pin "1") (pinfunction "1_1") (pintype "passive"))
      (node (ref "R6") (pin "2") (pinfunction "2_2") (pintype "passive"))
    )
    (net (code "19") (name "I_ABC_WET") (class "Default")
      (node (ref "IC7") (pin "1") (pinfunction "AMP/BIAS_1") (pintype "passive"))
      (node (ref "R25") (pin "2") (pinfunction "2_2") (pintype "passive"))
    )
    (net (code "20") (name "MIX_CV_IN") (class "Default")
      (node (ref "R5") (pin "1") (pinfunction "1_1") (pintype "passive"))
      (node (ref "X1") (pin "4") (pinfunction "1_4") (pintype "passive"))
    )
    (net (code "21") (name "Net-(C19-Pad2)") (class "Default")
      (node (ref "C19") (pin "2") (pinfunction "2_2") (pintype "passive"))
      (node (ref "D4") (pin "A") (pinfunction "A_A") (pintype "passive"))
      (node (ref "R57") (pin "2") (pinfunction "2_2") (pintype "passive"))
    )
    (net (code "22") (name "Net-(C21-Pad2)") (class "Default")
      (node (ref "C21") (pin "2") (pinfunction "2_2") (pintype "passive"))
      (node (ref "R3") (pin "1") (pinfunction "1_1") (pintype "passive"))
    )
    (net (code "23") (name "Net-(C22-Pad2)") (class "Default")
      (node (ref "C22") (pin "2") (pinfunction "2_2") (pintype "passive"))
      (node (ref "D3") (pin "A") (pinfunction "A_A") (pintype "passive"))
      (node (ref "R58") (pin "2") (pinfunction "2_2") (pintype "passive"))
    )
    (net (code "24") (name "Net-(C23-Pad2)") (class "Default")
      (node (ref "C23") (pin "2") (pinfunction "2_2") (pintype "passive"))
      (node (ref "R2") (pin "1") (pinfunction "1_1") (pintype "passive"))
    )
    (net (code "25") (name "Net-(D1-PadA)") (class "Default")
      (node (ref "D1") (pin "A") (pinfunction "A_A") (pintype "passive"))
      (node (ref "SV1") (pin "10") (pinfunction "10_10") (pintype "passive"))
      (node (ref "SV1") (pin "9") (pinfunction "9_9") (pintype "passive"))
    )
    (net (code "26") (name "Net-(D2-PadC)") (class "Default")
      (node (ref "D2") (pin "C") (pinfunction "C_C") (pintype "passive"))
      (node (ref "SV1") (pin "1") (pinfunction "1_1") (pintype "passive"))
      (node (ref "SV1") (pin "2") (pinfunction "2_2") (pintype "passive"))
    )
    (net (code "27") (name "Net-(D3-PadC)") (class "Default")
      (node (ref "D3") (pin "C") (pinfunction "C_C") (pintype "passive"))
      (node (ref "D4") (pin "C") (pinfunction "C_C") (pintype "passive"))
      (node (ref "R61") (pin "1") (pinfunction "1_1") (pintype "passive"))
    )
    (net (code "28") (name "Net-(IC1A--IN)") (class "Default")
      (node (ref "IC1") (pin "2") (pinfunction "-IN_2") (pintype "input"))
      (node (ref "R7") (pin "2") (pinfunction "2_2") (pintype "passive"))
      (node (ref "R8") (pin "2") (pinfunction "2_2") (pintype "passive"))
      (node (ref "R9") (pin "1") (pinfunction "1_1") (pintype "passive"))
    )
    (net (code "29") (name "Net-(IC1B--IN)") (class "Default")
      (node (ref "IC1") (pin "6") (pinfunction "-IN_6") (pintype "input"))
      (node (ref "IC7") (pin "12") (pinfunction "OUT_12") (pintype "output"))
      (node (ref "R16") (pin "1") (pinfunction "1_1") (pintype "passive"))
    )
    (net (code "30") (name "Net-(IC1B-OUT)") (class "Default")
      (node (ref "C21") (pin "1") (pinfunction "1_1") (pintype "passive"))
      (node (ref "IC1") (pin "7") (pinfunction "OUT_7") (pintype "output"))
      (node (ref "R16") (pin "2") (pinfunction "2_2") (pintype "passive"))
    )
    (net (code "31") (name "Net-(IC1C--IN)") (class "Default")
      (node (ref "IC1") (pin "9") (pinfunction "-IN_9") (pintype "input"))
      (node (ref "IC7") (pin "5") (pinfunction "OUT_5") (pintype "output"))
      (node (ref "R17") (pin "1") (pinfunction "1_1") (pintype "passive"))
    )
    (net (code "32") (name "Net-(IC1C-OUT)") (class "Default")
      (node (ref "C23") (pin "1") (pinfunction "1_1") (pintype "passive"))
      (node (ref "IC1") (pin "8") (pinfunction "OUT_8") (pintype "output"))
      (node (ref "R17") (pin "2") (pinfunction "2_2") (pintype "passive"))
    )
    (net (code "33") (name "Net-(IC1D--IN)") (class "Default")
      (node (ref "C25") (pin "1") (pinfunction "1_1") (pintype "passive"))
      (node (ref "IC1") (pin "13") (pinfunction "-IN_13") (pintype "input"))
      (node (ref "R1") (pin "1") (pinfunction "1_1") (pintype "passive"))
      (node (ref "R2") (pin "2") (pinfunction "2_2") (pintype "passive"))
      (node (ref "R3") (pin "2") (pinfunction "2_2") (pintype "passive"))
    )
    (net (code "34") (name "Net-(IC2A--IN)") (class "Default")
      (node (ref "IC2") (pin "2") (pinfunction "-IN_2") (pintype "input"))
      (node (ref "JP2") (pin "1") (pinfunction "1_1") (pintype "passive"))
      (node (ref "R22") (pin "1") (pinfunction "1_1") (pintype "passive"))
      (node (ref "R23") (pin "2") (pinfunction "2_2") (pintype "passive"))
      (node (ref "R33") (pin "2") (pinfunction "2_2") (pintype "passive"))
    )
    (net (code "35") (name "Net-(IC2A-OUT)") (class "Default")
      (node (ref "IC2") (pin "1") (pinfunction "OUT_1") (pintype "output"))
      (node (ref "R22") (pin "2") (pinfunction "2_2") (pintype "passive"))
      (node (ref "R26") (pin "1") (pinfunction "1_1") (pintype "passive"))
    )
    (net (code "36") (name "Net-(IC2B--IN)") (class "Default")
      (node (ref "IC2") (pin "6") (pinfunction "-IN_6") (pintype "input"))
      (node (ref "R38") (pin "1") (pinfunction "1_1") (pintype "passive"))
      (node (ref "R39") (pin "2") (pinfunction "2_2") (pintype "passive"))
      (node (ref "R47") (pin "2") (pinfunction "2_2") (pintype "passive"))
    )
    (net (code "37") (name "Net-(IC2C--IN)") (class "Default")
      (node (ref "IC2") (pin "9") (pinfunction "-IN_9") (pintype "input"))
      (node (ref "R4") (pin "2") (pinfunction "2_2") (pintype "passive"))
      (node (ref "R5") (pin "2") (pinfunction "2_2") (pintype "passive"))
      (node (ref "R6") (pin "1") (pinfunction "1_1") (pintype "passive"))
    )
    (net (code "38") (name "Net-(IC2D--IN)") (class "Default")
      (node (ref "IC2") (pin "13") (pinfunction "-IN_13") (pintype "input"))
      (node (ref "JP1") (pin "1") (pinfunction "1_1") (pintype "passive"))
      (node (ref "R18") (pin "1") (pinfunction "1_1") (pintype "passive"))
      (node (ref "R21") (pin "2") (pinfunction "2_2") (pintype "passive"))
      (node (ref "R34") (pin "2") (pinfunction "2_2") (pintype "passive"))
    )
    (net (code "39") (name "Net-(IC2D-OUT)") (class "Default")
      (node (ref "IC2") (pin "14") (pinfunction "OUT_14") (pintype "output"))
      (node (ref "R18") (pin "2") (pinfunction "2_2") (pintype "passive"))
      (node (ref "R25") (pin "1") (pinfunction "1_1") (pintype "passive"))
    )
    (net (code "40") (name "Net-(IC3A--IN)") (class "Default")
      (node (ref "IC3") (pin "2") (pinfunction "-IN_2") (pintype "input"))
      (node (ref "R40") (pin "2") (pinfunction "2_2") (pintype "passive"))
      (node (ref "R64") (pin "2") (pinfunction "2_2") (pintype "passive"))
      (node (ref "R65") (pin "1") (pinfunction "1_1") (pintype "passive"))
    )
    (net (code "41") (name "Net-(IC3A-OUT)") (class "Default")
      (node (ref "IC3") (pin "1") (pinfunction "OUT_1") (pintype "output"))
      (node (ref "R27") (pin "1") (pinfunction "1_1") (pintype "passive"))
      (node (ref "R65") (pin "2") (pinfunction "2_2") (pintype "passive"))
    )
    (net (code "42") (name "Net-(IC3B--IN)") (class "Default")
      (node (ref "IC3") (pin "6") (pinfunction "-IN_6") (pintype "input"))
      (node (ref "R11") (pin "2") (pinfunction "2_2") (pintype "passive"))
      (node (ref "R12") (pin "2") (pinfunction "2_2") (pintype "passive"))
      (node (ref "R13") (pin "1") (pinfunction "1_1") (pintype "passive"))
    )
    (net (code "43") (name "Net-(IC3C--IN)") (class "Default")
      (node (ref "IC3") (pin "9") (pinfunction "-IN_9") (pintype "input"))
      (node (ref "R10") (pin "2") (pinfunction "2_2") (pintype "passive"))
      (node (ref "R14") (pin "1") (pinfunction "1_1") (pintype "passive"))
      (node (ref "R15") (pin "2") (pinfunction "2_2") (pintype "passive"))
    )
    (net (code "44") (name "Net-(IC3C-OUT)") (class "Default")
      (node (ref "IC3") (pin "8") (pinfunction "OUT_8") (pintype "output"))
      (node (ref "R14") (pin "2") (pinfunction "2_2") (pintype "passive"))
      (node (ref "R56") (pin "1") (pinfunction "1_1") (pintype "passive"))
    )
    (net (code "45") (name "Net-(IC3D-+IN)") (class "Default")
      (node (ref "IC3") (pin "12") (pinfunction "+IN_12") (pintype "input"))
      (node (ref "R56") (pin "2") (pinfunction "2_2") (pintype "passive"))
    )
    (net (code "46") (name "Net-(IC3D--IN)") (class "Default")
      (node (ref "IC3") (pin "13") (pinfunction "-IN_13") (pintype "input"))
      (node (ref "R59") (pin "1") (pinfunction "1_1") (pintype "passive"))
      (node (ref "R61") (pin "2") (pinfunction "2_2") (pintype "passive"))
    )
    (net (code "47") (name "Net-(IC3D-OUT)") (class "Default")
      (node (ref "C24") (pin "1") (pinfunction "1_1") (pintype "passive"))
      (node (ref "IC3") (pin "14") (pinfunction "OUT_14") (pintype "output"))
      (node (ref "R59") (pin "2") (pinfunction "2_2") (pintype "passive"))
    )
    (net (code "48") (name "Net-(IC4A--IN)") (class "Default")
      (node (ref "IC4") (pin "2") (pinfunction "-IN_2") (pintype "input"))
      (node (ref "R45") (pin "2") (pinfunction "2_2") (pintype "passive"))
      (node (ref "R46") (pin "1") (pinfunction "1_1") (pintype "passive"))
    )
    (net (code "49") (name "Net-(IC4B--IN)") (class "Default")
      (node (ref "IC4") (pin "6") (pinfunction "-IN_6") (pintype "input"))
      (node (ref "IC4") (pin "7") (pinfunction "OUT_7") (pintype "output"))
    )
    (net (code "50") (name "Net-(IC4C--IN)") (class "Default")
      (node (ref "IC4") (pin "9") (pinfunction "-IN_9") (pintype "input"))
      (node (ref "IC6") (pin "12") (pinfunction "OUT_12") (pintype "output"))
      (node (ref "R63") (pin "1") (pinfunction "1_1") (pintype "passive"))
    )
    (net (code "51") (name "Net-(IC4D-+IN)") (class "Default")
      (node (ref "C17") (pin "2") (pinfunction "2_2") (pintype "passive"))
      (node (ref "IC4") (pin "12") (pinfunction "+IN_12") (pintype "input"))
      (node (ref "R44") (pin "2") (pinfunction "2_2") (pintype "passive"))
    )
    (net (code "52") (name "Net-(IC4D--IN)") (class "Default")
      (node (ref "IC4") (pin "13") (pinfunction "-IN_13") (pintype "input"))
      (node (ref "IC4") (pin "14") (pinfunction "OUT_14") (pintype "output"))
      (node (ref "R42") (pin "1") (pinfunction "1_1") (pintype "passive"))
      (node (ref "R43") (pin "1") (pinfunction "1_1") (pintype "passive"))
    )
    (net (code "53") (name "Net-(IC5A-+IN)") (class "Default")
      (node (ref "C20") (pin "1") (pinfunction "1_1") (pintype "passive"))
      (node (ref "IC5") (pin "3") (pinfunction "+IN_3") (pintype "input"))
      (node (ref "R28") (pin "2") (pinfunction "2_2") (pintype "passive"))
      (node (ref "R66") (pin "2") (pinfunction "2_2") (pintype "passive"))
    )
    (net (code "54") (name "Net-(IC5B-+IN)") (class "Default")
      (node (ref "IC5") (pin "14") (pinfunction "OUT_14") (pintype "output"))
      (node (ref "IC5") (pin "5") (pinfunction "+IN_5") (pintype "input"))
      (node (ref "R41") (pin "2") (pinfunction "2_2") (pintype "passive"))
    )
    (net (code "55") (name "Net-(IC5B--IN)") (class "Default")
      (node (ref "D6") (pin "C") (pinfunction "C_C") (pintype "passive"))
      (node (ref "IC5") (pin "6") (pinfunction "-IN_6") (pintype "input"))
      (node (ref "R66") (pin "1") (pinfunction "1_1") (pintype "passive"))
    )
    (net (code "56") (name "Net-(IC5B-OUT)") (class "Default")
      (node (ref "D6") (pin "A") (pinfunction "A_A") (pintype "passive"))
      (node (ref "IC5") (pin "7") (pinfunction "OUT_7") (pintype "output"))
    )
    (net (code "57") (name "Net-(IC5C--IN)") (class "Default")
      (node (ref "D5") (pin "C") (pinfunction "C_C") (pintype "passive"))
      (node (ref "IC5") (pin "12") (pinfunction "+IN_12") (pintype "input"))
      (node (ref "IC5") (pin "9") (pinfunction "-IN_9") (pintype "input"))
      (node (ref "R43") (pin "2") (pinfunction "2_2") (pintype "passive"))
    )
    (net (code "58") (name "Net-(IC5C-OUT)") (class "Default")
      (node (ref "D5") (pin "A") (pinfunction "A_A") (pintype "passive"))
      (node (ref "IC5") (pin "8") (pinfunction "OUT_8") (pintype "output"))
    )
    (net (code "59") (name "Net-(IC5D--IN)") (class "Default")
      (node (ref "IC5") (pin "13") (pinfunction "-IN_13") (pintype "input"))
      (node (ref "R41") (pin "1") (pinfunction "1_1") (pintype "passive"))
      (node (ref "R42") (pin "2") (pinfunction "2_2") (pintype "passive"))
    )
    (net (code "60") (name "Net-(IC6A-BUFF{slash}IN)") (class "Default")
      (node (ref "IC6") (pin "7") (pinfunction "BUFF/IN_7") (pintype "input"))
      (node (ref "IC6") (pin "8") (pinfunction "BUFF/OUT_8") (pintype "output"))
    )
    (net (code "61") (name "Net-(IC6B-+IN)") (class "Default")
      (node (ref "IC6") (pin "14") (pinfunction "+IN_14") (pintype "input"))
      (node (ref "R48") (pin "2") (pinfunction "2_2") (pintype "passive"))
    )
    (net (code "62") (name "Net-(IC6B--IN)") (class "Default")
      (node (ref "IC6") (pin "13") (pinfunction "-IN_13") (pintype "input"))
      (node (ref "R24") (pin "2") (pinfunction "2_2") (pintype "passive"))
      (node (ref "R49") (pin "2") (pinfunction "2_2") (pintype "passive"))
    )
    (net (code "63") (name "Net-(IC6B-BUFF{slash}IN)") (class "Default")
      (node (ref "IC6") (pin "10") (pinfunction "BUFF/IN_10") (pintype "input"))
      (node (ref "IC6") (pin "9") (pinfunction "BUFF/OUT_9") (pintype "output"))
    )
    (net (code "64") (name "Net-(IC6B-DIODE{slash}BIAS)") (class "Default")
      (node (ref "IC6") (pin "15") (pinfunction "DIODE/BIAS_15") (pintype "passive"))
      (node (ref "R31") (pin "2") (pinfunction "2_2") (pintype "passive"))
    )
    (net (code "65") (name "Net-(IC7A-+IN)") (class "Default")
      (node (ref "IC7") (pin "3") (pinfunction "+IN_3") (pintype "input"))
      (node (ref "R20") (pin "2") (pinfunction "2_2") (pintype "passive"))
      (node (ref "R53") (pin "2") (pinfunction "2_2") (pintype "passive"))
    )
    (net (code "66") (name "Net-(IC7A--IN)") (class "Default")
      (node (ref "IC7") (pin "4") (pinfunction "-IN_4") (pintype "input"))
      (node (ref "R52") (pin "2") (pinfunction "2_2") (pintype "passive"))
    )
    (net (code "67") (name "Net-(IC7A-BUFF{slash}IN)") (class "Default")
      (node (ref "IC7") (pin "7") (pinfunction "BUFF/IN_7") (pintype "input"))
      (node (ref "IC7") (pin "8") (pinfunction "BUFF/OUT_8") (pintype "output"))
    )
    (net (code "68") (name "Net-(IC7A-DIODE{slash}BIAS)") (class "Default")
      (node (ref "IC7") (pin "2") (pinfunction "DIODE/BIAS_2") (pintype "passive"))
      (node (ref "R29") (pin "2") (pinfunction "2_2") (pintype "passive"))
    )
    (net (code "69") (name "Net-(IC7B-+IN)") (class "Default")
      (node (ref "IC7") (pin "14") (pinfunction "+IN_14") (pintype "input"))
      (node (ref "R51") (pin "2") (pinfunction "2_2") (pintype "passive"))
    )
    (net (code "70") (name "Net-(IC7B--IN)") (class "Default")
      (node (ref "IC7") (pin "13") (pinfunction "-IN_13") (pintype "input"))
      (node (ref "R19") (pin "2") (pinfunction "2_2") (pintype "passive"))
      (node (ref "R50") (pin "2") (pinfunction "2_2") (pintype "passive"))
    )
    (net (code "71") (name "Net-(IC7B-BUFF{slash}IN)") (class "Default")
      (node (ref "IC7") (pin "10") (pinfunction "BUFF/IN_10") (pintype "input"))
      (node (ref "IC7") (pin "9") (pinfunction "BUFF/OUT_9") (pintype "output"))
    )
    (net (code "72") (name "Net-(IC7B-DIODE{slash}BIAS)") (class "Default")
      (node (ref "IC7") (pin "15") (pinfunction "DIODE/BIAS_15") (pintype "passive"))
      (node (ref "R30") (pin "2") (pinfunction "2_2") (pintype "passive"))
    )
    (net (code "73") (name "Net-(JP1-Pad2)") (class "Default")
      (node (ref "JP1") (pin "2") (pinfunction "2_2") (pintype "passive"))
      (node (ref "R35") (pin "2") (pinfunction "2_2") (pintype "passive"))
    )
    (net (code "74") (name "Net-(JP2-Pad2)") (class "Default")
      (node (ref "JP2") (pin "2") (pinfunction "2_2") (pintype "passive"))
      (node (ref "R32") (pin "2") (pinfunction "2_2") (pintype "passive"))
    )
    (net (code "75") (name "Net-(Q1-B)") (class "Default")
      (node (ref "C18") (pin "2") (pinfunction "2_2") (pintype "passive"))
      (node (ref "Q1") (pin "1") (pinfunction "B_1") (pintype "passive"))
      (node (ref "R60") (pin "1") (pinfunction "1_1") (pintype "passive"))
      (node (ref "R62") (pin "2") (pinfunction "2_2") (pintype "passive"))
    )
    (net (code "76") (name "Net-(Q1-C)") (class "Default")
      (node (ref "C19") (pin "1") (pinfunction "1_1") (pintype "passive"))
      (node (ref "Q1") (pin "3") (pinfunction "C_3") (pintype "passive"))
      (node (ref "R37") (pin "1") (pinfunction "1_1") (pintype "passive"))
      (node (ref "R57") (pin "1") (pinfunction "1_1") (pintype "passive"))
      (node (ref "R58") (pin "1") (pinfunction "1_1") (pintype "passive"))
    )
    (net (code "77") (name "Net-(Q1-E)") (class "Default")
      (node (ref "C22") (pin "1") (pinfunction "1_1") (pintype "passive"))
      (node (ref "Q1") (pin "2") (pinfunction "E_2") (pintype "passive"))
      (node (ref "R36") (pin "2") (pinfunction "2_2") (pintype "passive"))
    )
    (net (code "78") (name "Net-(RV1-S)") (class "Default")
      (node (ref "R11") (pin "1") (pinfunction "1_1") (pintype "passive"))
      (node (ref "RV1") (pin "2") (pinfunction "S_2") (pintype "passive"))
    )
    (net (code "79") (name "Net-(RV2-S)") (class "Default")
      (node (ref "R12") (pin "1") (pinfunction "1_1") (pintype "passive"))
      (node (ref "RV2") (pin "2") (pinfunction "S_2") (pintype "passive"))
    )
    (net (code "80") (name "Net-(RV3-A)") (class "Default")
      (node (ref "R54") (pin "2") (pinfunction "2_2") (pintype "passive"))
      (node (ref "RV3") (pin "1") (pinfunction "A_1") (pintype "passive"))
    )
    (net (code "81") (name "Net-(RV3-E)") (class "Default")
      (node (ref "R55") (pin "1") (pinfunction "1_1") (pintype "passive"))
      (node (ref "RV3") (pin "3") (pinfunction "E_3") (pintype "passive"))
    )
    (net (code "82") (name "Net-(RV3-S)") (class "Default")
      (node (ref "R10") (pin "1") (pinfunction "1_1") (pintype "passive"))
      (node (ref "RV3") (pin "2") (pinfunction "S_2") (pintype "passive"))
    )
    (net (code "83") (name "Net-(RV4-S)") (class "Default")
      (node (ref "R15") (pin "1") (pinfunction "1_1") (pintype "passive"))
      (node (ref "RV4") (pin "2") (pinfunction "S_2") (pintype "passive"))
    )
    (net (code "84") (name "Net-(RV5-S)") (class "Default")
      (node (ref "R4") (pin "1") (pinfunction "1_1") (pintype "passive"))
      (node (ref "RV5") (pin "2") (pinfunction "S_2") (pintype "passive"))
    )
    (net (code "85") (name "WET") (class "Default")
      (node (ref "C24") (pin "2") (pinfunction "2_2") (pintype "passive"))
      (node (ref "R20") (pin "1") (pinfunction "1_1") (pintype "passive"))
    )
    (net (code "86") (name "unconnected-(IC6A-+IN-Pad3)") (class "Default")
      (node (ref "IC6") (pin "3") (pinfunction "+IN_3") (pintype "input"))
    )
    (net (code "87") (name "unconnected-(IC6A--IN-Pad4)") (class "Default")
      (node (ref "IC6") (pin "4") (pinfunction "-IN_4") (pintype "input"))
    )
    (net (code "88") (name "unconnected-(IC6A-DIODE{slash}BIAS-Pad2)") (class "Default")
      (node (ref "IC6") (pin "2") (pinfunction "DIODE/BIAS_2") (pintype "passive"))
    )
    (net (code "89") (name "unconnected-(IC6A-OUT-Pad5)") (class "Default")
      (node (ref "IC6") (pin "5") (pinfunction "OUT_5") (pintype "output"))
    )
    (net (code "90") (name "unconnected-(SV1-Pad11)") (class "Default")
      (node (ref "SV1") (pin "11") (pinfunction "11_11") (pintype "passive"))
    )
    (net (code "91") (name "unconnected-(SV1-Pad12)") (class "Default")
      (node (ref "SV1") (pin "12") (pinfunction "12_12") (pintype "passive"))
    )
    (net (code "92") (name "unconnected-(SV1-Pad13)") (class "Default")
      (node (ref "SV1") (pin "13") (pinfunction "13_13") (pintype "passive"))
    )
    (net (code "93") (name "unconnected-(SV1-Pad14)") (class "Default")
      (node (ref "SV1") (pin "14") (pinfunction "14_14") (pintype "passive"))
    )
    (net (code "94") (name "unconnected-(SV1-Pad15)") (class "Default")
      (node (ref "SV1") (pin "15") (pinfunction "15_15") (pintype "passive"))
    )
    (net (code "95") (name "unconnected-(SV1-Pad16)") (class "Default")
      (node (ref "SV1") (pin "16") (pinfunction "16_16") (pintype "passive"))
    )
  )
)
